# Bootselector.net
KiCad netlist of a schematic drawn in EAGLE
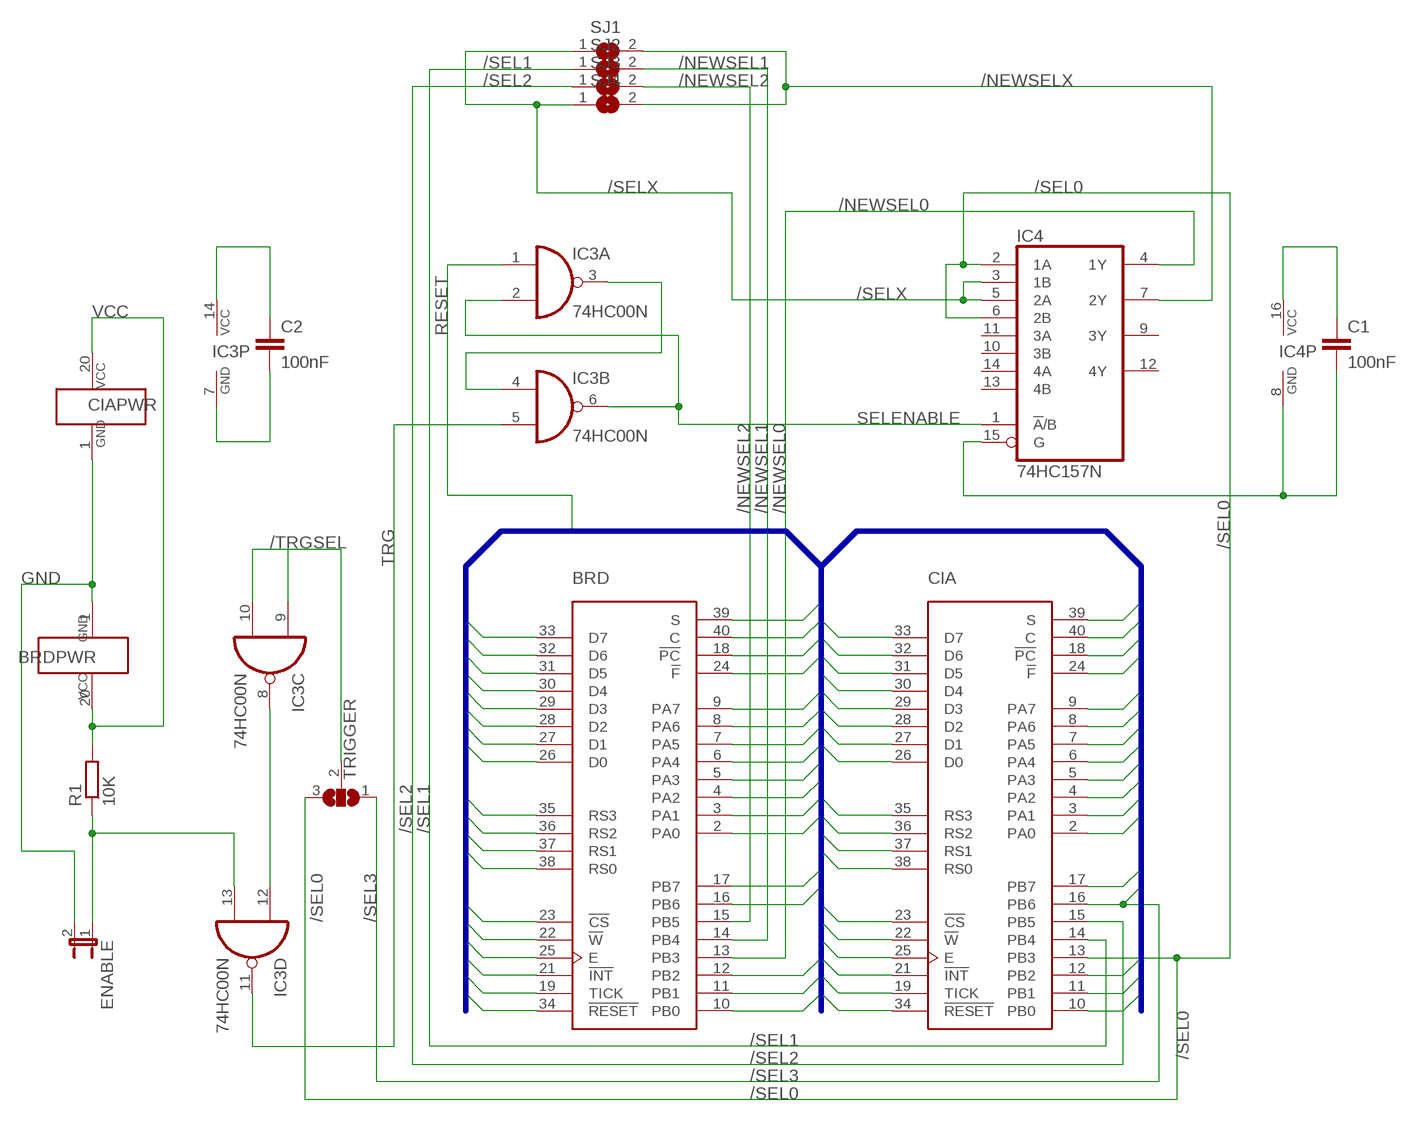
[diagram p0: schematic, sheet 1]

(export (version "E")
  (design (tool "Eeschema 10.0.6"))
  (components
    (comp (ref "BRD")
      (value "CIA_DIP")
      (footprint "eagle-import:DIP40-6")
      (libsource (lib "eagle-import") (part "CIA_DIP"))
    )
    (comp (ref "C1")
      (value "100nF")
      (footprint "eagle-import:C050-025X075")
      (libsource (lib "eagle-import") (part "C-EU050-025X075"))
    )
    (comp (ref "C2")
      (value "100nF")
      (footprint "eagle-import:C050-025X075")
      (libsource (lib "eagle-import") (part "C-EU050-025X075"))
    )
    (comp (ref "CIA")
      (value "CIA_DIP")
      (footprint "eagle-import:DIP40-6")
      (libsource (lib "eagle-import") (part "CIA_DIP"))
    )
    (comp (ref "ENABLE")
      (value "JP1E")
      (footprint "eagle-import:JP1")
      (libsource (lib "eagle-import") (part "JP1E"))
    )
    (comp (ref "IC3")
      (value "74HC00N")
      (footprint "eagle-import:DIL14")
      (libsource (lib "eagle-import") (part "7400NHC"))
    )
    (comp (ref "IC4")
      (value "74HC157N")
      (footprint "eagle-import:DIL16")
      (libsource (lib "eagle-import") (part "74157NHC"))
    )
    (comp (ref "R1")
      (value "10K")
      (footprint "eagle-import:0207_10")
      (libsource (lib "eagle-import") (part "R-EU_0207/10"))
    )
    (comp (ref "SJ1") (value "SJ") (footprint "eagle-import:SJ") (libsource (lib "eagle-import") (part "SJ")))
    (comp (ref "SJ2") (value "SJ") (footprint "eagle-import:SJ") (libsource (lib "eagle-import") (part "SJ")))
    (comp (ref "SJ3") (value "SJ") (footprint "eagle-import:SJ") (libsource (lib "eagle-import") (part "SJ")))
    (comp (ref "SJ4") (value "SJ") (footprint "eagle-import:SJ") (libsource (lib "eagle-import") (part "SJ")))
    (comp (ref "TRIGGER")
      (value "SJ2W")
      (footprint "eagle-import:SJ_2")
      (libsource (lib "eagle-import") (part "SJ2W"))
    )
  )
  (nets
    (net (code "1") (name "/C") (class "Default")
      (node (ref "BRD") (pin "40") (pinfunction "C_40") (pintype "bidirectional"))
      (node (ref "CIA") (pin "40") (pinfunction "C_40") (pintype "bidirectional"))
    )
    (net (code "2") (name "/CS") (class "Default")
      (node (ref "BRD") (pin "23") (pinfunction "~{CS}_23") (pintype "input"))
      (node (ref "CIA") (pin "23") (pinfunction "~{CS}_23") (pintype "input"))
    )
    (net (code "3") (name "/D0") (class "Default")
      (node (ref "BRD") (pin "26") (pinfunction "D0_26") (pintype "bidirectional"))
      (node (ref "CIA") (pin "26") (pinfunction "D0_26") (pintype "bidirectional"))
    )
    (net (code "4") (name "/D1") (class "Default")
      (node (ref "BRD") (pin "27") (pinfunction "D1_27") (pintype "bidirectional"))
      (node (ref "CIA") (pin "27") (pinfunction "D1_27") (pintype "bidirectional"))
    )
    (net (code "5") (name "/D2") (class "Default")
      (node (ref "BRD") (pin "28") (pinfunction "D2_28") (pintype "bidirectional"))
      (node (ref "CIA") (pin "28") (pinfunction "D2_28") (pintype "bidirectional"))
    )
    (net (code "6") (name "/D3") (class "Default")
      (node (ref "BRD") (pin "29") (pinfunction "D3_29") (pintype "bidirectional"))
      (node (ref "CIA") (pin "29") (pinfunction "D3_29") (pintype "bidirectional"))
    )
    (net (code "7") (name "/D4") (class "Default")
      (node (ref "BRD") (pin "30") (pinfunction "D4_30") (pintype "bidirectional"))
      (node (ref "CIA") (pin "30") (pinfunction "D4_30") (pintype "bidirectional"))
    )
    (net (code "8") (name "/D5") (class "Default")
      (node (ref "BRD") (pin "31") (pinfunction "D5_31") (pintype "bidirectional"))
      (node (ref "CIA") (pin "31") (pinfunction "D5_31") (pintype "bidirectional"))
    )
    (net (code "9") (name "/D6") (class "Default")
      (node (ref "BRD") (pin "32") (pinfunction "D6_32") (pintype "bidirectional"))
      (node (ref "CIA") (pin "32") (pinfunction "D6_32") (pintype "bidirectional"))
    )
    (net (code "10") (name "/D7") (class "Default")
      (node (ref "BRD") (pin "33") (pinfunction "D7_33") (pintype "bidirectional"))
      (node (ref "CIA") (pin "33") (pinfunction "D7_33") (pintype "bidirectional"))
    )
    (net (code "11") (name "/E") (class "Default")
      (node (ref "BRD") (pin "25") (pinfunction "E_25") (pintype "input"))
      (node (ref "CIA") (pin "25") (pinfunction "E_25") (pintype "input"))
    )
    (net (code "12") (name "/F") (class "Default")
      (node (ref "BRD") (pin "24") (pinfunction "~{F}_24") (pintype "bidirectional"))
      (node (ref "CIA") (pin "24") (pinfunction "~{F}_24") (pintype "bidirectional"))
    )
    (net (code "13") (name "/GND") (class "Default")
      (node (ref "BRD") (pin "1") (pinfunction "GND1_1") (pintype "power_in"))
      (node (ref "C1") (pin "2") (pinfunction "2_2") (pintype "passive"))
      (node (ref "C2") (pin "2") (pinfunction "2_2") (pintype "passive"))
      (node (ref "CIA") (pin "1") (pinfunction "GND1_1") (pintype "power_in"))
      (node (ref "ENABLE") (pin "2") (pinfunction "2_2") (pintype "passive"))
      (node (ref "IC3") (pin "7") (pinfunction "GND_7") (pintype "power_in"))
      (node (ref "IC4") (pin "15") (pinfunction "G_15") (pintype "input"))
      (node (ref "IC4") (pin "8") (pinfunction "GND_8") (pintype "power_in"))
    )
    (net (code "14") (name "/INT") (class "Default")
      (node (ref "BRD") (pin "21") (pinfunction "~{INT}_21") (pintype "output"))
      (node (ref "CIA") (pin "21") (pinfunction "~{INT}_21") (pintype "output"))
    )
    (net (code "15") (name "/PA0") (class "Default")
      (node (ref "BRD") (pin "2") (pinfunction "PA0_2") (pintype "bidirectional"))
      (node (ref "CIA") (pin "2") (pinfunction "PA0_2") (pintype "bidirectional"))
    )
    (net (code "16") (name "/PA1") (class "Default")
      (node (ref "BRD") (pin "3") (pinfunction "PA1_3") (pintype "bidirectional"))
      (node (ref "CIA") (pin "3") (pinfunction "PA1_3") (pintype "bidirectional"))
    )
    (net (code "17") (name "/PA2") (class "Default")
      (node (ref "BRD") (pin "4") (pinfunction "PA2_4") (pintype "bidirectional"))
      (node (ref "CIA") (pin "4") (pinfunction "PA2_4") (pintype "bidirectional"))
    )
    (net (code "18") (name "/PA3") (class "Default")
      (node (ref "BRD") (pin "5") (pinfunction "PA3_5") (pintype "bidirectional"))
      (node (ref "CIA") (pin "5") (pinfunction "PA3_5") (pintype "bidirectional"))
    )
    (net (code "19") (name "/PA4") (class "Default")
      (node (ref "BRD") (pin "6") (pinfunction "PA4_6") (pintype "bidirectional"))
      (node (ref "CIA") (pin "6") (pinfunction "PA4_6") (pintype "bidirectional"))
    )
    (net (code "20") (name "/PA5") (class "Default")
      (node (ref "BRD") (pin "7") (pinfunction "PA5_7") (pintype "bidirectional"))
      (node (ref "CIA") (pin "7") (pinfunction "PA5_7") (pintype "bidirectional"))
    )
    (net (code "21") (name "/PA6") (class "Default")
      (node (ref "BRD") (pin "8") (pinfunction "PA6_8") (pintype "bidirectional"))
      (node (ref "CIA") (pin "8") (pinfunction "PA6_8") (pintype "bidirectional"))
    )
    (net (code "22") (name "/PA7") (class "Default")
      (node (ref "BRD") (pin "9") (pinfunction "PA7_9") (pintype "bidirectional"))
      (node (ref "CIA") (pin "9") (pinfunction "PA7_9") (pintype "bidirectional"))
    )
    (net (code "23") (name "/PB0") (class "Default")
      (node (ref "BRD") (pin "10") (pinfunction "PB0_10") (pintype "bidirectional"))
      (node (ref "CIA") (pin "10") (pinfunction "PB0_10") (pintype "bidirectional"))
    )
    (net (code "24") (name "/PB1") (class "Default")
      (node (ref "BRD") (pin "11") (pinfunction "PB1_11") (pintype "bidirectional"))
      (node (ref "CIA") (pin "11") (pinfunction "PB1_11") (pintype "bidirectional"))
    )
    (net (code "25") (name "/PB2") (class "Default")
      (node (ref "BRD") (pin "12") (pinfunction "PB2_12") (pintype "bidirectional"))
      (node (ref "CIA") (pin "12") (pinfunction "PB2_12") (pintype "bidirectional"))
    )
    (net (code "26") (name "/PB7") (class "Default")
      (node (ref "BRD") (pin "17") (pinfunction "PB7_17") (pintype "bidirectional"))
      (node (ref "CIA") (pin "17") (pinfunction "PB7_17") (pintype "bidirectional"))
    )
    (net (code "27") (name "/PC") (class "Default")
      (node (ref "BRD") (pin "18") (pinfunction "~{PC}_18") (pintype "bidirectional"))
      (node (ref "CIA") (pin "18") (pinfunction "~{PC}_18") (pintype "bidirectional"))
    )
    (net (code "28") (name "/RESET") (class "Default")
      (node (ref "BRD") (pin "34") (pinfunction "~{RESET}_34") (pintype "input"))
      (node (ref "CIA") (pin "34") (pinfunction "~{RESET}_34") (pintype "input"))
      (node (ref "IC3") (pin "1") (pinfunction "I0_1") (pintype "input"))
    )
    (net (code "29") (name "/RS0") (class "Default")
      (node (ref "BRD") (pin "38") (pinfunction "RS0_38") (pintype "input"))
      (node (ref "CIA") (pin "38") (pinfunction "RS0_38") (pintype "input"))
    )
    (net (code "30") (name "/RS1") (class "Default")
      (node (ref "BRD") (pin "37") (pinfunction "RS1_37") (pintype "input"))
      (node (ref "CIA") (pin "37") (pinfunction "RS1_37") (pintype "input"))
    )
    (net (code "31") (name "/RS2") (class "Default")
      (node (ref "BRD") (pin "36") (pinfunction "RS2_36") (pintype "input"))
      (node (ref "CIA") (pin "36") (pinfunction "RS2_36") (pintype "input"))
    )
    (net (code "32") (name "/RS3") (class "Default")
      (node (ref "BRD") (pin "35") (pinfunction "RS3_35") (pintype "input"))
      (node (ref "CIA") (pin "35") (pinfunction "RS3_35") (pintype "input"))
    )
    (net (code "33") (name "/S") (class "Default")
      (node (ref "BRD") (pin "39") (pinfunction "S_39") (pintype "bidirectional"))
      (node (ref "CIA") (pin "39") (pinfunction "S_39") (pintype "bidirectional"))
    )
    (net (code "34") (name "/SELENABLE") (class "Default")
      (node (ref "IC3") (pin "2") (pinfunction "I1_2") (pintype "input"))
      (node (ref "IC3") (pin "6") (pinfunction "O_6") (pintype "output"))
      (node (ref "IC4") (pin "1") (pinfunction "~{A}/B_1") (pintype "input"))
    )
    (net (code "35") (name "/TICK") (class "Default")
      (node (ref "BRD") (pin "19") (pinfunction "TICK_19") (pintype "input"))
      (node (ref "CIA") (pin "19") (pinfunction "TICK_19") (pintype "input"))
    )
    (net (code "36") (name "/TRG") (class "Default")
      (node (ref "IC3") (pin "11") (pinfunction "O_11") (pintype "output"))
      (node (ref "IC3") (pin "5") (pinfunction "I1_5") (pintype "input"))
    )
    (net (code "37") (name "/VCC") (class "Default")
      (node (ref "BRD") (pin "20") (pinfunction "VCC1_20") (pintype "power_in"))
      (node (ref "C1") (pin "1") (pinfunction "1_1") (pintype "passive"))
      (node (ref "C2") (pin "1") (pinfunction "1_1") (pintype "passive"))
      (node (ref "CIA") (pin "20") (pinfunction "VCC1_20") (pintype "power_in"))
      (node (ref "IC3") (pin "14") (pinfunction "VCC_14") (pintype "power_in"))
      (node (ref "IC4") (pin "16") (pinfunction "VCC_16") (pintype "power_in"))
      (node (ref "R1") (pin "2") (pinfunction "2_2") (pintype "passive"))
    )
    (net (code "38") (name "/W") (class "Default")
      (node (ref "BRD") (pin "22") (pinfunction "~{W}_22") (pintype "input"))
      (node (ref "CIA") (pin "22") (pinfunction "~{W}_22") (pintype "input"))
    )
    (net (code "39") (name "/{slash}NEWSEL0") (class "Default")
      (node (ref "BRD") (pin "13") (pinfunction "PB3_13") (pintype "bidirectional"))
      (node (ref "IC4") (pin "4") (pinfunction "1Y_4") (pintype "output"))
    )
    (net (code "40") (name "/{slash}NEWSEL1") (class "Default")
      (node (ref "BRD") (pin "14") (pinfunction "PB4_14") (pintype "bidirectional"))
      (node (ref "SJ2") (pin "2") (pinfunction "2_2") (pintype "passive"))
    )
    (net (code "41") (name "/{slash}NEWSEL2") (class "Default")
      (node (ref "BRD") (pin "15") (pinfunction "PB5_15") (pintype "bidirectional"))
      (node (ref "SJ3") (pin "2") (pinfunction "2_2") (pintype "passive"))
    )
    (net (code "42") (name "/{slash}NEWSELX") (class "Default")
      (node (ref "IC4") (pin "7") (pinfunction "2Y_7") (pintype "output"))
      (node (ref "SJ1") (pin "2") (pinfunction "2_2") (pintype "passive"))
      (node (ref "SJ4") (pin "2") (pinfunction "2_2") (pintype "passive"))
    )
    (net (code "43") (name "/{slash}SEL0") (class "Default")
      (node (ref "CIA") (pin "13") (pinfunction "PB3_13") (pintype "bidirectional"))
      (node (ref "IC4") (pin "2") (pinfunction "1A_2") (pintype "input"))
      (node (ref "IC4") (pin "6") (pinfunction "2B_6") (pintype "input"))
      (node (ref "TRIGGER") (pin "3") (pinfunction "3_3") (pintype "passive"))
    )
    (net (code "44") (name "/{slash}SEL1") (class "Default")
      (node (ref "CIA") (pin "14") (pinfunction "PB4_14") (pintype "bidirectional"))
      (node (ref "SJ2") (pin "1") (pinfunction "1_1") (pintype "passive"))
    )
    (net (code "45") (name "/{slash}SEL2") (class "Default")
      (node (ref "CIA") (pin "15") (pinfunction "PB5_15") (pintype "bidirectional"))
      (node (ref "SJ3") (pin "1") (pinfunction "1_1") (pintype "passive"))
    )
    (net (code "46") (name "/{slash}SEL3") (class "Default")
      (node (ref "BRD") (pin "16") (pinfunction "PB6_16") (pintype "bidirectional"))
      (node (ref "CIA") (pin "16") (pinfunction "PB6_16") (pintype "bidirectional"))
      (node (ref "TRIGGER") (pin "1") (pinfunction "1_1") (pintype "passive"))
    )
    (net (code "47") (name "/{slash}SELX") (class "Default")
      (node (ref "IC4") (pin "3") (pinfunction "1B_3") (pintype "input"))
      (node (ref "IC4") (pin "5") (pinfunction "2A_5") (pintype "input"))
      (node (ref "SJ1") (pin "1") (pinfunction "1_1") (pintype "passive"))
      (node (ref "SJ4") (pin "1") (pinfunction "1_1") (pintype "passive"))
    )
    (net (code "48") (name "/{slash}TRGSEL") (class "Default")
      (node (ref "IC3") (pin "10") (pinfunction "I1_10") (pintype "input"))
      (node (ref "IC3") (pin "9") (pinfunction "I0_9") (pintype "input"))
      (node (ref "TRIGGER") (pin "2") (pinfunction "2_2") (pintype "passive"))
    )
    (net (code "49") (name "Net-(IC3A-O)") (class "Default")
      (node (ref "IC3") (pin "3") (pinfunction "O_3") (pintype "output"))
      (node (ref "IC3") (pin "4") (pinfunction "I0_4") (pintype "input"))
    )
    (net (code "50") (name "Net-(IC3C-O)") (class "Default")
      (node (ref "IC3") (pin "12") (pinfunction "I0_12") (pintype "input"))
      (node (ref "IC3") (pin "8") (pinfunction "O_8") (pintype "output"))
    )
    (net (code "51") (name "Net-(IC3D-I1)") (class "Default")
      (node (ref "ENABLE") (pin "1") (pinfunction "1_1") (pintype "passive"))
      (node (ref "IC3") (pin "13") (pinfunction "I1_13") (pintype "input"))
      (node (ref "R1") (pin "1") (pinfunction "1_1") (pintype "passive"))
    )
    (net (code "52") (name "unconnected-(IC4A-3A-Pad11)") (class "Default")
      (node (ref "IC4") (pin "11") (pinfunction "3A_11") (pintype "input"))
    )
    (net (code "53") (name "unconnected-(IC4A-3B-Pad10)") (class "Default")
      (node (ref "IC4") (pin "10") (pinfunction "3B_10") (pintype "input"))
    )
    (net (code "54") (name "unconnected-(IC4A-3Y-Pad9)") (class "Default")
      (node (ref "IC4") (pin "9") (pinfunction "3Y_9") (pintype "output"))
    )
    (net (code "55") (name "unconnected-(IC4A-4A-Pad14)") (class "Default")
      (node (ref "IC4") (pin "14") (pinfunction "4A_14") (pintype "input"))
    )
    (net (code "56") (name "unconnected-(IC4A-4B-Pad13)") (class "Default")
      (node (ref "IC4") (pin "13") (pinfunction "4B_13") (pintype "input"))
    )
    (net (code "57") (name "unconnected-(IC4A-4Y-Pad12)") (class "Default")
      (node (ref "IC4") (pin "12") (pinfunction "4Y_12") (pintype "output"))
    )
  )
)
